# PLD_Connectors_PC-104.net
KiCad netlist of a schematic drawn in Altium Designer
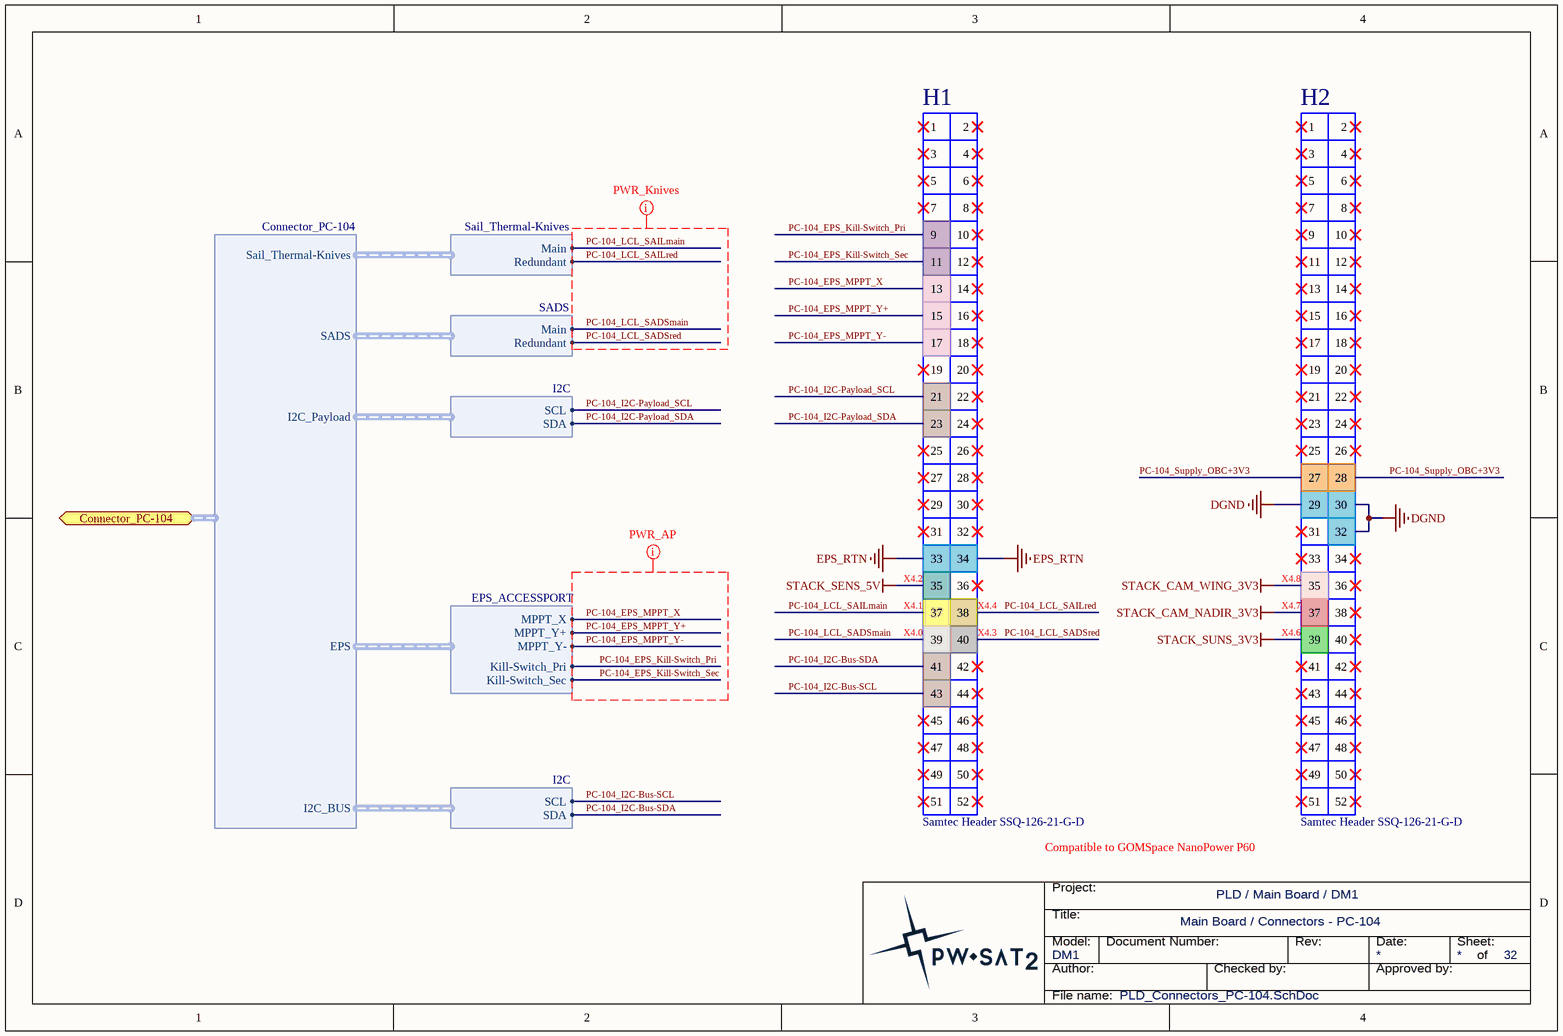
[diagram p0: PLD_Connectors_PC-104.SchDoc]

(export (version "E")
  (design (tool "Eeschema 10.0.6"))
  (components
    (comp (ref "H1")
      (value "Samtec Header SSQ-126-21-G-D")
      (footprint "Samtec_SSQ-126-21-G-D")
      (description "Samtec SSQ Series Header , 2.54mm pitch, 2x26pin. PC-104 Stack Connector.")
      (libsource (lib "connectors_printed-circuit-board") (part "Samtec_SSQ-126-xx-x-D"))
    )
    (comp (ref "H2")
      (value "Samtec Header SSQ-126-21-G-D")
      (footprint "Samtec_SSQ-126-21-G-D")
      (description "Samtec SSQ Series Header , 2.54mm pitch, 2x26pin. PC-104 Stack Connector.")
      (libsource (lib "connectors_printed-circuit-board") (part "Samtec_SSQ-126-xx-x-D"))
    )
  )
  (nets
    (net (code "7") (name "/PC-104_EPS_Kill-Switch_Pri") (class "Default")
      (node (ref "H1") (pin "9") (pinfunction "9_9") (pintype "passive"))
    )
    (net (code "8") (name "/PC-104_EPS_Kill-Switch_Sec") (class "Default")
      (node (ref "H1") (pin "11") (pinfunction "11_11") (pintype "passive"))
    )
    (net (code "9") (name "/PC-104_EPS_MPPT_X") (class "Default")
      (node (ref "H1") (pin "13") (pinfunction "13_13") (pintype "passive"))
    )
    (net (code "10") (name "/PC-104_EPS_MPPT_Y+") (class "Default")
      (node (ref "H1") (pin "15") (pinfunction "15_15") (pintype "passive"))
    )
    (net (code "11") (name "/PC-104_EPS_MPPT_Y-") (class "Default")
      (node (ref "H1") (pin "17") (pinfunction "17_17") (pintype "passive"))
    )
    (net (code "12") (name "/PC-104_I2C-Bus-SCL") (class "Default")
      (node (ref "H1") (pin "43") (pinfunction "43_43") (pintype "passive"))
    )
    (net (code "13") (name "/PC-104_I2C-Bus-SDA") (class "Default")
      (node (ref "H1") (pin "41") (pinfunction "41_41") (pintype "passive"))
    )
    (net (code "14") (name "/PC-104_I2C-Payload_SCL") (class "Default")
      (node (ref "H1") (pin "21") (pinfunction "21_21") (pintype "passive"))
    )
    (net (code "15") (name "/PC-104_I2C-Payload_SDA") (class "Default")
      (node (ref "H1") (pin "23") (pinfunction "23_23") (pintype "passive"))
    )
    (net (code "16") (name "/PC-104_LCL_SADSmain") (class "Default")
      (node (ref "H1") (pin "39") (pinfunction "39_39") (pintype "passive"))
    )
    (net (code "17") (name "/PC-104_LCL_SADSred") (class "Default")
      (node (ref "H1") (pin "40") (pinfunction "40_40") (pintype "passive"))
    )
    (net (code "18") (name "/PC-104_LCL_SAILmain") (class "Default")
      (node (ref "H1") (pin "37") (pinfunction "37_37") (pintype "passive"))
    )
    (net (code "19") (name "/PC-104_LCL_SAILred") (class "Default")
      (node (ref "H1") (pin "38") (pinfunction "38_38") (pintype "passive"))
    )
    (net (code "20") (name "/PC-104_Supply_OBC+3V3") (class "Default")
      (node (ref "H2") (pin "27") (pinfunction "27_27") (pintype "passive"))
      (node (ref "H2") (pin "28") (pinfunction "28_28") (pintype "passive"))
    )
    (net (code "25") (name "DGND") (class "Default")
      (node (ref "H2") (pin "29") (pinfunction "29_29") (pintype "passive"))
      (node (ref "H2") (pin "30") (pinfunction "30_30") (pintype "passive"))
      (node (ref "H2") (pin "32") (pinfunction "32_32") (pintype "passive"))
    )
    (net (code "26") (name "EPS_RTN") (class "Default")
      (node (ref "H1") (pin "33") (pinfunction "33_33") (pintype "passive"))
      (node (ref "H1") (pin "34") (pinfunction "34_34") (pintype "passive"))
    )
    (net (code "27") (name "STACK_CAM_NADIR_3V3") (class "Default")
      (node (ref "H2") (pin "37") (pinfunction "37_37") (pintype "passive"))
    )
    (net (code "28") (name "STACK_CAM_WING_3V3") (class "Default")
      (node (ref "H2") (pin "35") (pinfunction "35_35") (pintype "passive"))
    )
    (net (code "29") (name "STACK_SENS_5V") (class "Default")
      (node (ref "H1") (pin "35") (pinfunction "35_35") (pintype "passive"))
    )
    (net (code "30") (name "STACK_SUNS_3V3") (class "Default")
      (node (ref "H2") (pin "39") (pinfunction "39_39") (pintype "passive"))
    )
    (net (code "31") (name "unconnected-(H1-Pad1)") (class "Default")
      (node (ref "H1") (pin "1") (pinfunction "1_1") (pintype "passive+no_connect"))
    )
    (net (code "32") (name "unconnected-(H1-Pad2)") (class "Default")
      (node (ref "H1") (pin "2") (pinfunction "2_2") (pintype "passive+no_connect"))
    )
    (net (code "33") (name "unconnected-(H1-Pad3)") (class "Default")
      (node (ref "H1") (pin "3") (pinfunction "3_3") (pintype "passive+no_connect"))
    )
    (net (code "34") (name "unconnected-(H1-Pad4)") (class "Default")
      (node (ref "H1") (pin "4") (pinfunction "4_4") (pintype "passive+no_connect"))
    )
    (net (code "35") (name "unconnected-(H1-Pad5)") (class "Default")
      (node (ref "H1") (pin "5") (pinfunction "5_5") (pintype "passive+no_connect"))
    )
    (net (code "36") (name "unconnected-(H1-Pad6)") (class "Default")
      (node (ref "H1") (pin "6") (pinfunction "6_6") (pintype "passive+no_connect"))
    )
    (net (code "37") (name "unconnected-(H1-Pad7)") (class "Default")
      (node (ref "H1") (pin "7") (pinfunction "7_7") (pintype "passive+no_connect"))
    )
    (net (code "38") (name "unconnected-(H1-Pad8)") (class "Default")
      (node (ref "H1") (pin "8") (pinfunction "8_8") (pintype "passive+no_connect"))
    )
    (net (code "39") (name "unconnected-(H1-Pad10)") (class "Default")
      (node (ref "H1") (pin "10") (pinfunction "10_10") (pintype "passive+no_connect"))
    )
    (net (code "40") (name "unconnected-(H1-Pad12)") (class "Default")
      (node (ref "H1") (pin "12") (pinfunction "12_12") (pintype "passive+no_connect"))
    )
    (net (code "41") (name "unconnected-(H1-Pad14)") (class "Default")
      (node (ref "H1") (pin "14") (pinfunction "14_14") (pintype "passive+no_connect"))
    )
    (net (code "42") (name "unconnected-(H1-Pad16)") (class "Default")
      (node (ref "H1") (pin "16") (pinfunction "16_16") (pintype "passive+no_connect"))
    )
    (net (code "43") (name "unconnected-(H1-Pad18)") (class "Default")
      (node (ref "H1") (pin "18") (pinfunction "18_18") (pintype "passive+no_connect"))
    )
    (net (code "44") (name "unconnected-(H1-Pad19)") (class "Default")
      (node (ref "H1") (pin "19") (pinfunction "19_19") (pintype "passive+no_connect"))
    )
    (net (code "45") (name "unconnected-(H1-Pad20)") (class "Default")
      (node (ref "H1") (pin "20") (pinfunction "20_20") (pintype "passive+no_connect"))
    )
    (net (code "46") (name "unconnected-(H1-Pad22)") (class "Default")
      (node (ref "H1") (pin "22") (pinfunction "22_22") (pintype "passive+no_connect"))
    )
    (net (code "47") (name "unconnected-(H1-Pad24)") (class "Default")
      (node (ref "H1") (pin "24") (pinfunction "24_24") (pintype "passive+no_connect"))
    )
    (net (code "48") (name "unconnected-(H1-Pad25)") (class "Default")
      (node (ref "H1") (pin "25") (pinfunction "25_25") (pintype "passive+no_connect"))
    )
    (net (code "49") (name "unconnected-(H1-Pad26)") (class "Default")
      (node (ref "H1") (pin "26") (pinfunction "26_26") (pintype "passive+no_connect"))
    )
    (net (code "50") (name "unconnected-(H1-Pad27)") (class "Default")
      (node (ref "H1") (pin "27") (pinfunction "27_27") (pintype "passive+no_connect"))
    )
    (net (code "51") (name "unconnected-(H1-Pad28)") (class "Default")
      (node (ref "H1") (pin "28") (pinfunction "28_28") (pintype "passive+no_connect"))
    )
    (net (code "52") (name "unconnected-(H1-Pad29)") (class "Default")
      (node (ref "H1") (pin "29") (pinfunction "29_29") (pintype "passive+no_connect"))
    )
    (net (code "53") (name "unconnected-(H1-Pad30)") (class "Default")
      (node (ref "H1") (pin "30") (pinfunction "30_30") (pintype "passive+no_connect"))
    )
    (net (code "54") (name "unconnected-(H1-Pad31)") (class "Default")
      (node (ref "H1") (pin "31") (pinfunction "31_31") (pintype "passive+no_connect"))
    )
    (net (code "55") (name "unconnected-(H1-Pad32)") (class "Default")
      (node (ref "H1") (pin "32") (pinfunction "32_32") (pintype "passive+no_connect"))
    )
    (net (code "56") (name "unconnected-(H1-Pad36)") (class "Default")
      (node (ref "H1") (pin "36") (pinfunction "36_36") (pintype "passive+no_connect"))
    )
    (net (code "57") (name "unconnected-(H1-Pad42)") (class "Default")
      (node (ref "H1") (pin "42") (pinfunction "42_42") (pintype "passive+no_connect"))
    )
    (net (code "58") (name "unconnected-(H1-Pad44)") (class "Default")
      (node (ref "H1") (pin "44") (pinfunction "44_44") (pintype "passive+no_connect"))
    )
    (net (code "59") (name "unconnected-(H1-Pad45)") (class "Default")
      (node (ref "H1") (pin "45") (pinfunction "45_45") (pintype "passive+no_connect"))
    )
    (net (code "60") (name "unconnected-(H1-Pad46)") (class "Default")
      (node (ref "H1") (pin "46") (pinfunction "46_46") (pintype "passive+no_connect"))
    )
    (net (code "61") (name "unconnected-(H1-Pad47)") (class "Default")
      (node (ref "H1") (pin "47") (pinfunction "47_47") (pintype "passive+no_connect"))
    )
    (net (code "62") (name "unconnected-(H1-Pad48)") (class "Default")
      (node (ref "H1") (pin "48") (pinfunction "48_48") (pintype "passive+no_connect"))
    )
    (net (code "63") (name "unconnected-(H1-Pad49)") (class "Default")
      (node (ref "H1") (pin "49") (pinfunction "49_49") (pintype "passive+no_connect"))
    )
    (net (code "64") (name "unconnected-(H1-Pad50)") (class "Default")
      (node (ref "H1") (pin "50") (pinfunction "50_50") (pintype "passive+no_connect"))
    )
    (net (code "65") (name "unconnected-(H1-Pad51)") (class "Default")
      (node (ref "H1") (pin "51") (pinfunction "51_51") (pintype "passive+no_connect"))
    )
    (net (code "66") (name "unconnected-(H1-Pad52)") (class "Default")
      (node (ref "H1") (pin "52") (pinfunction "52_52") (pintype "passive+no_connect"))
    )
    (net (code "67") (name "unconnected-(H2-Pad1)") (class "Default")
      (node (ref "H2") (pin "1") (pinfunction "1_1") (pintype "passive+no_connect"))
    )
    (net (code "68") (name "unconnected-(H2-Pad2)") (class "Default")
      (node (ref "H2") (pin "2") (pinfunction "2_2") (pintype "passive+no_connect"))
    )
    (net (code "69") (name "unconnected-(H2-Pad3)") (class "Default")
      (node (ref "H2") (pin "3") (pinfunction "3_3") (pintype "passive+no_connect"))
    )
    (net (code "70") (name "unconnected-(H2-Pad4)") (class "Default")
      (node (ref "H2") (pin "4") (pinfunction "4_4") (pintype "passive+no_connect"))
    )
    (net (code "71") (name "unconnected-(H2-Pad5)") (class "Default")
      (node (ref "H2") (pin "5") (pinfunction "5_5") (pintype "passive+no_connect"))
    )
    (net (code "72") (name "unconnected-(H2-Pad6)") (class "Default")
      (node (ref "H2") (pin "6") (pinfunction "6_6") (pintype "passive+no_connect"))
    )
    (net (code "73") (name "unconnected-(H2-Pad7)") (class "Default")
      (node (ref "H2") (pin "7") (pinfunction "7_7") (pintype "passive+no_connect"))
    )
    (net (code "74") (name "unconnected-(H2-Pad8)") (class "Default")
      (node (ref "H2") (pin "8") (pinfunction "8_8") (pintype "passive+no_connect"))
    )
    (net (code "75") (name "unconnected-(H2-Pad9)") (class "Default")
      (node (ref "H2") (pin "9") (pinfunction "9_9") (pintype "passive+no_connect"))
    )
    (net (code "76") (name "unconnected-(H2-Pad10)") (class "Default")
      (node (ref "H2") (pin "10") (pinfunction "10_10") (pintype "passive+no_connect"))
    )
    (net (code "77") (name "unconnected-(H2-Pad11)") (class "Default")
      (node (ref "H2") (pin "11") (pinfunction "11_11") (pintype "passive+no_connect"))
    )
    (net (code "78") (name "unconnected-(H2-Pad12)") (class "Default")
      (node (ref "H2") (pin "12") (pinfunction "12_12") (pintype "passive+no_connect"))
    )
    (net (code "79") (name "unconnected-(H2-Pad13)") (class "Default")
      (node (ref "H2") (pin "13") (pinfunction "13_13") (pintype "passive+no_connect"))
    )
    (net (code "80") (name "unconnected-(H2-Pad14)") (class "Default")
      (node (ref "H2") (pin "14") (pinfunction "14_14") (pintype "passive+no_connect"))
    )
    (net (code "81") (name "unconnected-(H2-Pad15)") (class "Default")
      (node (ref "H2") (pin "15") (pinfunction "15_15") (pintype "passive+no_connect"))
    )
    (net (code "82") (name "unconnected-(H2-Pad16)") (class "Default")
      (node (ref "H2") (pin "16") (pinfunction "16_16") (pintype "passive+no_connect"))
    )
    (net (code "83") (name "unconnected-(H2-Pad17)") (class "Default")
      (node (ref "H2") (pin "17") (pinfunction "17_17") (pintype "passive+no_connect"))
    )
    (net (code "84") (name "unconnected-(H2-Pad18)") (class "Default")
      (node (ref "H2") (pin "18") (pinfunction "18_18") (pintype "passive+no_connect"))
    )
    (net (code "85") (name "unconnected-(H2-Pad19)") (class "Default")
      (node (ref "H2") (pin "19") (pinfunction "19_19") (pintype "passive+no_connect"))
    )
    (net (code "86") (name "unconnected-(H2-Pad20)") (class "Default")
      (node (ref "H2") (pin "20") (pinfunction "20_20") (pintype "passive+no_connect"))
    )
    (net (code "87") (name "unconnected-(H2-Pad21)") (class "Default")
      (node (ref "H2") (pin "21") (pinfunction "21_21") (pintype "passive+no_connect"))
    )
    (net (code "88") (name "unconnected-(H2-Pad22)") (class "Default")
      (node (ref "H2") (pin "22") (pinfunction "22_22") (pintype "passive+no_connect"))
    )
    (net (code "89") (name "unconnected-(H2-Pad23)") (class "Default")
      (node (ref "H2") (pin "23") (pinfunction "23_23") (pintype "passive+no_connect"))
    )
    (net (code "90") (name "unconnected-(H2-Pad24)") (class "Default")
      (node (ref "H2") (pin "24") (pinfunction "24_24") (pintype "passive+no_connect"))
    )
    (net (code "91") (name "unconnected-(H2-Pad25)") (class "Default")
      (node (ref "H2") (pin "25") (pinfunction "25_25") (pintype "passive+no_connect"))
    )
    (net (code "92") (name "unconnected-(H2-Pad26)") (class "Default")
      (node (ref "H2") (pin "26") (pinfunction "26_26") (pintype "passive+no_connect"))
    )
    (net (code "93") (name "unconnected-(H2-Pad31)") (class "Default")
      (node (ref "H2") (pin "31") (pinfunction "31_31") (pintype "passive+no_connect"))
    )
    (net (code "94") (name "unconnected-(H2-Pad33)") (class "Default")
      (node (ref "H2") (pin "33") (pinfunction "33_33") (pintype "passive+no_connect"))
    )
    (net (code "95") (name "unconnected-(H2-Pad34)") (class "Default")
      (node (ref "H2") (pin "34") (pinfunction "34_34") (pintype "passive+no_connect"))
    )
    (net (code "96") (name "unconnected-(H2-Pad36)") (class "Default")
      (node (ref "H2") (pin "36") (pinfunction "36_36") (pintype "passive+no_connect"))
    )
    (net (code "97") (name "unconnected-(H2-Pad38)") (class "Default")
      (node (ref "H2") (pin "38") (pinfunction "38_38") (pintype "passive+no_connect"))
    )
    (net (code "98") (name "unconnected-(H2-Pad40)") (class "Default")
      (node (ref "H2") (pin "40") (pinfunction "40_40") (pintype "passive+no_connect"))
    )
    (net (code "99") (name "unconnected-(H2-Pad41)") (class "Default")
      (node (ref "H2") (pin "41") (pinfunction "41_41") (pintype "passive+no_connect"))
    )
    (net (code "100") (name "unconnected-(H2-Pad42)") (class "Default")
      (node (ref "H2") (pin "42") (pinfunction "42_42") (pintype "passive+no_connect"))
    )
    (net (code "101") (name "unconnected-(H2-Pad43)") (class "Default")
      (node (ref "H2") (pin "43") (pinfunction "43_43") (pintype "passive+no_connect"))
    )
    (net (code "102") (name "unconnected-(H2-Pad44)") (class "Default")
      (node (ref "H2") (pin "44") (pinfunction "44_44") (pintype "passive+no_connect"))
    )
    (net (code "103") (name "unconnected-(H2-Pad45)") (class "Default")
      (node (ref "H2") (pin "45") (pinfunction "45_45") (pintype "passive+no_connect"))
    )
    (net (code "104") (name "unconnected-(H2-Pad46)") (class "Default")
      (node (ref "H2") (pin "46") (pinfunction "46_46") (pintype "passive+no_connect"))
    )
    (net (code "105") (name "unconnected-(H2-Pad47)") (class "Default")
      (node (ref "H2") (pin "47") (pinfunction "47_47") (pintype "passive+no_connect"))
    )
    (net (code "106") (name "unconnected-(H2-Pad48)") (class "Default")
      (node (ref "H2") (pin "48") (pinfunction "48_48") (pintype "passive+no_connect"))
    )
    (net (code "107") (name "unconnected-(H2-Pad49)") (class "Default")
      (node (ref "H2") (pin "49") (pinfunction "49_49") (pintype "passive+no_connect"))
    )
    (net (code "108") (name "unconnected-(H2-Pad50)") (class "Default")
      (node (ref "H2") (pin "50") (pinfunction "50_50") (pintype "passive+no_connect"))
    )
    (net (code "109") (name "unconnected-(H2-Pad51)") (class "Default")
      (node (ref "H2") (pin "51") (pinfunction "51_51") (pintype "passive+no_connect"))
    )
    (net (code "110") (name "unconnected-(H2-Pad52)") (class "Default")
      (node (ref "H2") (pin "52") (pinfunction "52_52") (pintype "passive+no_connect"))
    )
  )
)
